# TLM_002_DS3231SN_RTC.net
KiCad netlist of a schematic drawn in Altium Designer
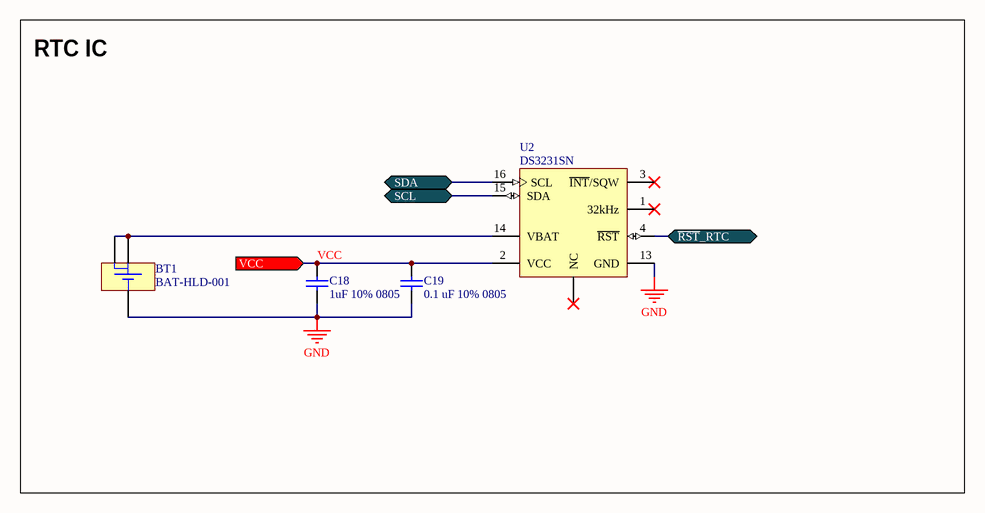
[diagram p0: TLM_002_DS3231SN_RTC.SchDoc]

(export (version "E")
  (design (tool "Eeschema 10.0.6"))
  (components
    (comp (ref "BT1")
      (value "BAT-HLD-001")
      (footprint "BATHLD-001")
      (description "20mm Coin Cell Battery Holder")
      (libsource (lib "Altium Content Vault") (part "BATHLD-001"))
    )
    (comp (ref "C18")
      (value "1uF 10% 0805")
      (footprint "CAPC2013X145X50NL20T20")
      (fields (field (name "PART NUMBER") "VJ0805Y105KXQRW1BC") (field (name "MANUFACTURER") "Vitramon"))
      (libsource (lib "Altium Content Vault") (part "CAP"))
    )
    (comp (ref "C19")
      (value "0.1 uF 10% 0805")
      (footprint "CAPC2013X140X50ML20T25")
      (fields
        (field (name "PART NUMBER") "0805DD104KAT2A")
        (field (name "MANUFACTURER") "AVX Interconnect / Elco")
      )
      (libsource (lib "Altium Content Vault") (part "CAP"))
    )
    (comp (ref "U2")
      (value "DS3231SN")
      (footprint "W16#H2_N")
      (description "DS3231 Series 5.5 V Extremely Accurate I2C-Integrated RTC/TCXO/Crystal - SOIC-16")
      (libsource (lib "NAZAR LYSENKO") (part "MAX-RTC-16-DS3231S-W16#H2"))
    )
  )
  (nets
    (net (code "1") (name "/SCL") (class "Default")
      (node (ref "U2") (pin "15") (pinfunction "SDA_15") (pintype "bidirectional"))
    )
    (net (code "2") (name "/SDA") (class "Default")
      (node (ref "U2") (pin "16") (pinfunction "SCL_16") (pintype "input"))
    )
    (net (code "3") (name "/VCC") (class "Default")
      (node (ref "C18") (pin "2") (pinfunction "2_2") (pintype "passive"))
      (node (ref "C19") (pin "2") (pinfunction "2_2") (pintype "passive"))
      (node (ref "U2") (pin "2") (pinfunction "VCC_2") (pintype "passive"))
    )
    (net (code "4") (name "/~{RST}_RTC") (class "Default")
      (node (ref "U2") (pin "4") (pinfunction "~{RST}_4") (pintype "bidirectional"))
    )
    (net (code "5") (name "GND") (class "Default")
      (node (ref "BT1") (pin "1") (pinfunction "-_1") (pintype "passive"))
      (node (ref "C18") (pin "1") (pinfunction "1_1") (pintype "passive"))
      (node (ref "C19") (pin "1") (pinfunction "1_1") (pintype "passive"))
      (node (ref "U2") (pin "13") (pinfunction "GND_13") (pintype "power_in"))
    )
    (net (code "6") (name "Net-(U2-VBAT)") (class "Default")
      (node (ref "BT1") (pin "2") (pinfunction "+_2") (pintype "passive"))
      (node (ref "BT1") (pin "3") (pinfunction "+_3") (pintype "passive"))
      (node (ref "U2") (pin "14") (pinfunction "VBAT_14") (pintype "power_in"))
    )
    (net (code "7") (name "unconnected-(U2-32kHz-Pad1)") (class "Default")
      (node (ref "U2") (pin "1") (pinfunction "32kHz_1") (pintype "open_collector+no_connect"))
    )
    (net (code "8") (name "unconnected-(U2-NC-Pad5)") (class "Default")
      (node (ref "U2") (pin "5") (pinfunction "NC_5") (pintype "passive+no_connect"))
    )
    (net (code "9") (name "unconnected-(U2-~{INT}{slash}SQW-Pad3)") (class "Default")
      (node (ref "U2") (pin "3") (pinfunction "~{INT}/SQW_3") (pintype "open_collector+no_connect"))
    )
  )
)
